# Programmer_Debugger.net
KiCad netlist of a schematic drawn in Altium Designer
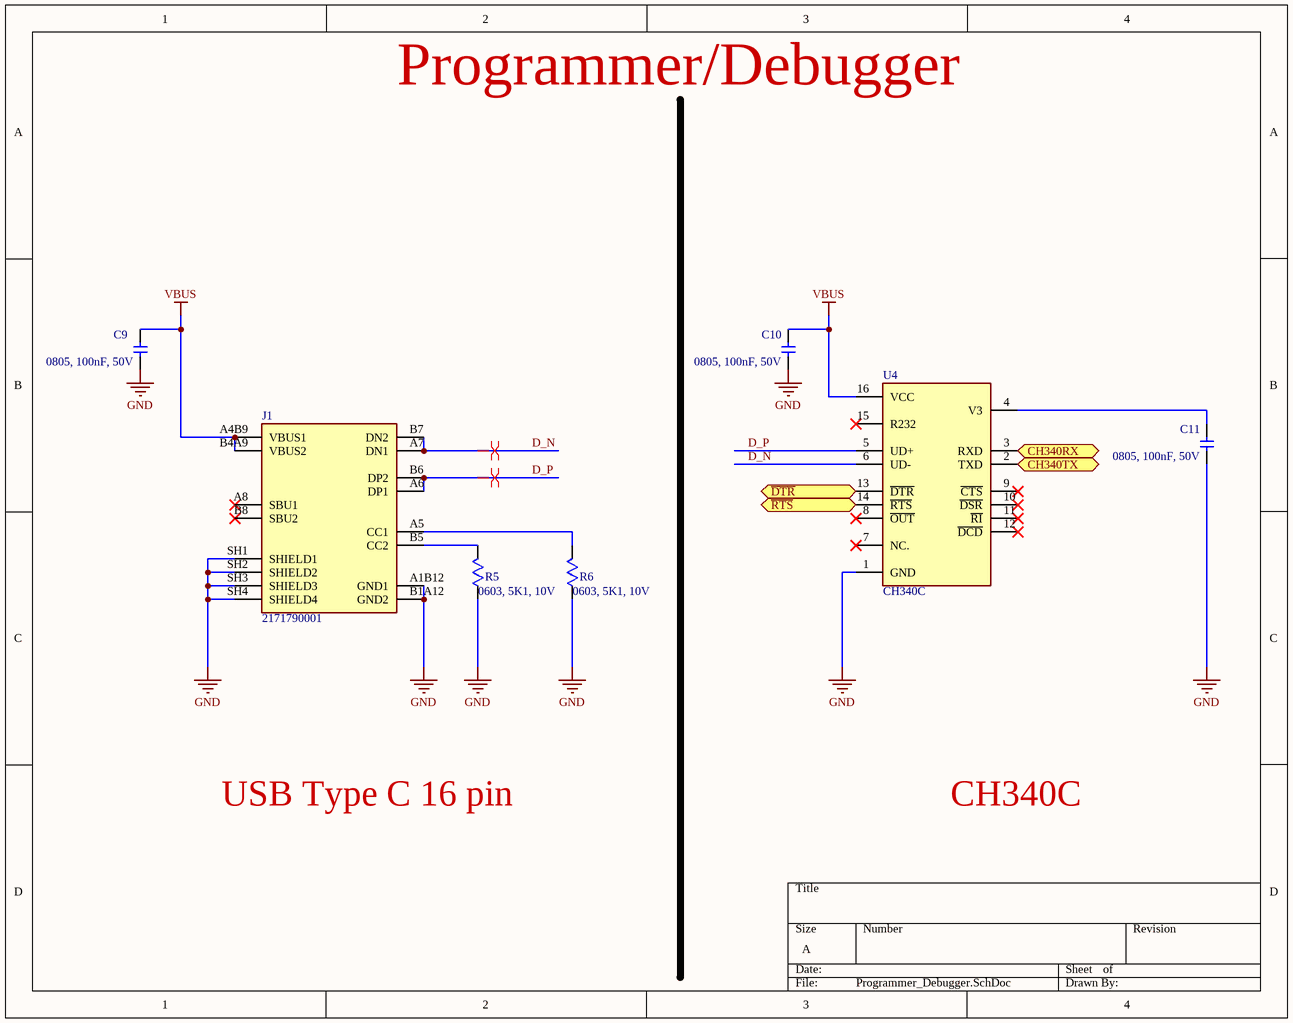
[diagram p0: Programmer_Debugger.SchDoc]

(export (version "E")
  (design (tool "Eeschema 10.0.6"))
  (components
    (comp (ref "C9")
      (value "0805, 100nF, 50V")
      (footprint "C0805")
      (description "C0805")
      (libsource (lib "STM32F103 Blue Pill Library") (part "C0805"))
    )
    (comp (ref "C10")
      (value "0805, 100nF, 50V")
      (footprint "C0805")
      (description "C0805")
      (libsource (lib "STM32F103 Blue Pill Library") (part "C0805"))
    )
    (comp (ref "C11")
      (value "0805, 100nF, 50V")
      (footprint "C0805")
      (description "C0805")
      (libsource (lib "STM32F103 Blue Pill Library") (part "C0805"))
    )
    (comp (ref "J1")
      (value "2171790001")
      (footprint "MOLEX_2171790001")
      (description "USB Type C - Connector, Top-mount SMT, 16pos ¦ Molex Incorporated 217179-0001")
      (fields (field (name "MF") "Molex") (field (name "MP") "217179-0001"))
      (libsource (lib "ESP_LoRa_schematic_lib") (part "2171790001"))
    )
    (comp (ref "R5")
      (value "0603, 5K1, 10V")
      (footprint "RES0603")
      (description "R0603")
      (libsource (lib "STM32F103 Blue Pill Library") (part "R0603"))
    )
    (comp (ref "R6")
      (value "0603, 5K1, 10V")
      (footprint "RES0603")
      (description "R0603")
      (libsource (lib "STM32F103 Blue Pill Library") (part "R0603"))
    )
    (comp (ref "U4")
      (value "CH340C")
      (footprint "SOIC127P600X180-16N")
      (description "USB to serial chip CH340")
      (fields (field (name "MF") "WCH"))
      (libsource (lib "ESP_LoRa_schematic_lib") (part "CH340C"))
    )
  )
  (nets
    (net (code "1") (name "/CH340RX") (class "Default")
      (node (ref "U4") (pin "3") (pinfunction "RXD_3") (pintype "passive"))
    )
    (net (code "2") (name "/CH340TX") (class "Default")
      (node (ref "U4") (pin "2") (pinfunction "TXD_2") (pintype "passive"))
    )
    (net (code "3") (name "/D_N") (class "Default")
      (node (ref "J1") (pin "A7") (pinfunction "DN1_A7") (pintype "passive"))
      (node (ref "J1") (pin "B7") (pinfunction "DN2_B7") (pintype "passive"))
      (node (ref "U4") (pin "6") (pinfunction "UD-_6") (pintype "passive"))
    )
    (net (code "4") (name "/D_P") (class "Default")
      (node (ref "J1") (pin "A6") (pinfunction "DP1_A6") (pintype "passive"))
      (node (ref "J1") (pin "B6") (pinfunction "DP2_B6") (pintype "passive"))
      (node (ref "U4") (pin "5") (pinfunction "UD+_5") (pintype "passive"))
    )
    (net (code "5") (name "/~{DTR}") (class "Default")
      (node (ref "U4") (pin "13") (pinfunction "~{DTR}_13") (pintype "passive"))
    )
    (net (code "6") (name "/~{RTS}") (class "Default")
      (node (ref "U4") (pin "14") (pinfunction "~{RTS}_14") (pintype "passive"))
    )
    (net (code "7") (name "GND") (class "Default")
      (node (ref "C10") (pin "1") (pinfunction "1_1") (pintype "passive"))
      (node (ref "C11") (pin "1") (pinfunction "1_1") (pintype "passive"))
      (node (ref "C9") (pin "1") (pinfunction "1_1") (pintype "passive"))
      (node (ref "J1") (pin "A1B12") (pinfunction "GND1_A1B12") (pintype "passive"))
      (node (ref "J1") (pin "B1A12") (pinfunction "GND2_B1A12") (pintype "passive"))
      (node (ref "J1") (pin "SH1") (pinfunction "SHIELD1_SH1") (pintype "passive"))
      (node (ref "J1") (pin "SH2") (pinfunction "SHIELD2_SH2") (pintype "passive"))
      (node (ref "J1") (pin "SH3") (pinfunction "SHIELD3_SH3") (pintype "passive"))
      (node (ref "J1") (pin "SH4") (pinfunction "SHIELD4_SH4") (pintype "passive"))
      (node (ref "R5") (pin "1") (pinfunction "1_1") (pintype "passive"))
      (node (ref "R6") (pin "1") (pinfunction "1_1") (pintype "passive"))
      (node (ref "U4") (pin "1") (pinfunction "GND_1") (pintype "passive"))
    )
    (net (code "8") (name "Net-(J1-CC1)") (class "Default")
      (node (ref "J1") (pin "A5") (pinfunction "CC1_A5") (pintype "passive"))
      (node (ref "R6") (pin "2") (pinfunction "2_2") (pintype "passive"))
    )
    (net (code "9") (name "Net-(J1-CC2)") (class "Default")
      (node (ref "J1") (pin "B5") (pinfunction "CC2_B5") (pintype "passive"))
      (node (ref "R5") (pin "2") (pinfunction "2_2") (pintype "passive"))
    )
    (net (code "10") (name "Net-(U4-V3)") (class "Default")
      (node (ref "C11") (pin "2") (pinfunction "2_2") (pintype "passive"))
      (node (ref "U4") (pin "4") (pinfunction "V3_4") (pintype "passive"))
    )
    (net (code "11") (name "VBUS") (class "Default")
      (node (ref "C10") (pin "2") (pinfunction "2_2") (pintype "passive"))
      (node (ref "C9") (pin "2") (pinfunction "2_2") (pintype "passive"))
      (node (ref "J1") (pin "A4B9") (pinfunction "VBUS1_A4B9") (pintype "passive"))
      (node (ref "J1") (pin "B4A9") (pinfunction "VBUS2_B4A9") (pintype "passive"))
      (node (ref "U4") (pin "16") (pinfunction "VCC_16") (pintype "passive"))
    )
    (net (code "12") (name "unconnected-(J1-SBU1-PadA8)") (class "Default")
      (node (ref "J1") (pin "A8") (pinfunction "SBU1_A8") (pintype "passive+no_connect"))
    )
    (net (code "13") (name "unconnected-(J1-SBU2-PadB8)") (class "Default")
      (node (ref "J1") (pin "B8") (pinfunction "SBU2_B8") (pintype "passive+no_connect"))
    )
    (net (code "14") (name "unconnected-(U4-NC.-Pad7)") (class "Default")
      (node (ref "U4") (pin "7") (pinfunction "NC._7") (pintype "passive+no_connect"))
    )
    (net (code "15") (name "unconnected-(U4-R232-Pad15)") (class "Default")
      (node (ref "U4") (pin "15") (pinfunction "R232_15") (pintype "passive+no_connect"))
    )
    (net (code "16") (name "unconnected-(U4-~{CTS}-Pad9)") (class "Default")
      (node (ref "U4") (pin "9") (pinfunction "~{CTS}_9") (pintype "passive+no_connect"))
    )
    (net (code "17") (name "unconnected-(U4-~{DCD}-Pad12)") (class "Default")
      (node (ref "U4") (pin "12") (pinfunction "~{DCD}_12") (pintype "passive+no_connect"))
    )
    (net (code "18") (name "unconnected-(U4-~{DSR}-Pad10)") (class "Default")
      (node (ref "U4") (pin "10") (pinfunction "~{DSR}_10") (pintype "passive+no_connect"))
    )
    (net (code "19") (name "unconnected-(U4-~{OUT}-Pad8)") (class "Default")
      (node (ref "U4") (pin "8") (pinfunction "~{OUT}_8") (pintype "passive+no_connect"))
    )
    (net (code "20") (name "unconnected-(U4-~{RI}-Pad11)") (class "Default")
      (node (ref "U4") (pin "11") (pinfunction "~{RI}_11") (pintype "passive+no_connect"))
    )
  )
)
